# pcb_v3.net
KiCad netlist of a schematic drawn in EAGLE
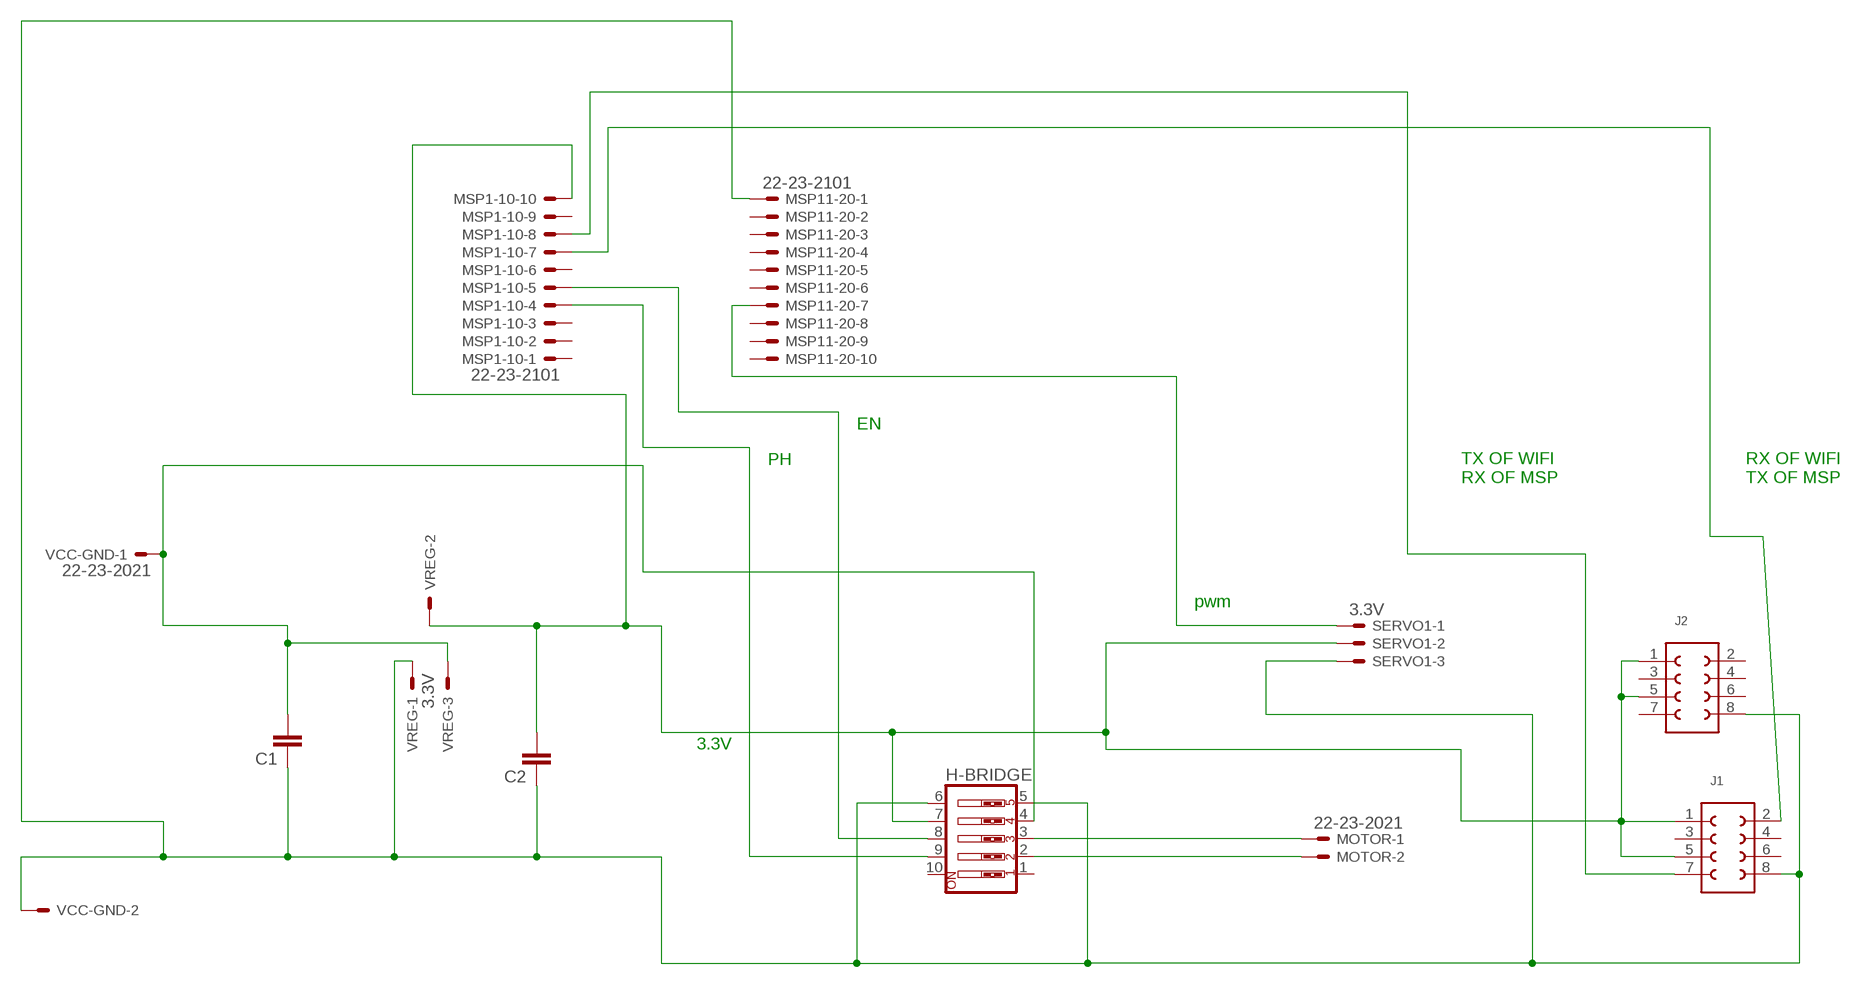
[diagram p0: schematic, sheet 1]

(export (version "E")
  (design (tool "Eeschema 10.0.6"))
  (components
    (comp (ref "C1")
      (value "C2,5-3")
      (footprint "eagle-import:C2.5-3")
      (libsource (lib "eagle-import") (part "C2,5-3"))
    )
    (comp (ref "C2")
      (value "C2,5-3")
      (footprint "eagle-import:C2.5-3")
      (libsource (lib "eagle-import") (part "C2,5-3"))
    )
    (comp (ref "H-BRIDGE")
      (value "SW_DIP-5")
      (footprint "eagle-import:EDG-05")
      (libsource (lib "eagle-import") (part "SW_DIP-5"))
    )
    (comp (ref "J1")
      (value "61300821121")
      (footprint "eagle-import:61300821121")
      (libsource (lib "eagle-import") (part "61300821121"))
    )
    (comp (ref "J2")
      (value "61300821121")
      (footprint "eagle-import:61300821121")
      (libsource (lib "eagle-import") (part "61300821121"))
    )
    (comp (ref "MOTOR")
      (value "22-23-2021")
      (footprint "eagle-import:22-23-2021")
      (fields (field (name "MF") "MOLEX"))
      (libsource (lib "eagle-import") (part "22-23-2021"))
    )
    (comp (ref "MSP1-10")
      (value "22-23-2101")
      (footprint "eagle-import:22-23-2101")
      (fields (field (name "MF") "MOLEX"))
      (libsource (lib "eagle-import") (part "22-23-2101"))
    )
    (comp (ref "MSP11-20")
      (value "22-23-2101")
      (footprint "eagle-import:22-23-2101")
      (fields (field (name "MF") "MOLEX"))
      (libsource (lib "eagle-import") (part "22-23-2101"))
    )
    (comp (ref "SERVO1")
      (value "3.3V")
      (footprint "eagle-import:22-23-2031")
      (fields (field (name "MF") "MOLEX") (field (name "MPN") "22-23-2031"))
      (libsource (lib "eagle-import") (part "22-23-2031"))
    )
    (comp (ref "VCC-GND")
      (value "22-23-2021")
      (footprint "eagle-import:22-23-2021")
      (fields (field (name "MF") "MOLEX"))
      (libsource (lib "eagle-import") (part "22-23-2021"))
    )
    (comp (ref "VREG")
      (value "3.3V")
      (footprint "eagle-import:22-23-2031")
      (fields (field (name "MF") "MOLEX") (field (name "MPN") "22-23-2031"))
      (libsource (lib "eagle-import") (part "22-23-2031"))
    )
  )
  (nets
    (net (code "1") (name "Net-(J1-3)") (class "Default")
      (node (ref "C2") (pin "2") (pinfunction "2_2") (pintype "passive"))
      (node (ref "H-BRIDGE") (pin "7") (pinfunction "7_7") (pintype "passive"))
      (node (ref "J1") (pin "1") (pinfunction "1_1") (pintype "passive"))
      (node (ref "J1") (pin "5") (pinfunction "3_5") (pintype "passive"))
      (node (ref "J2") (pin "1") (pinfunction "1_1") (pintype "passive"))
      (node (ref "J2") (pin "5") (pinfunction "3_5") (pintype "passive"))
      (node (ref "MSP1-10") (pin "10") (pinfunction "S_10") (pintype "passive"))
      (node (ref "SERVO1") (pin "2") (pinfunction "S_2") (pintype "passive"))
      (node (ref "VREG") (pin "2") (pinfunction "S_2") (pintype "passive"))
    )
    (net (code "2") (name "Net-(J1-4)") (class "Default")
      (node (ref "J1") (pin "7") (pinfunction "4_7") (pintype "passive"))
      (node (ref "MSP1-10") (pin "8") (pinfunction "S_8") (pintype "passive"))
    )
    (net (code "3") (name "Net-(J1-5)") (class "Default")
      (node (ref "C1") (pin "1") (pinfunction "1_1") (pintype "passive"))
      (node (ref "C2") (pin "1") (pinfunction "1_1") (pintype "passive"))
      (node (ref "H-BRIDGE") (pin "5") (pinfunction "5_5") (pintype "passive"))
      (node (ref "H-BRIDGE") (pin "6") (pinfunction "6_6") (pintype "passive"))
      (node (ref "J1") (pin "8") (pinfunction "5_8") (pintype "passive"))
      (node (ref "J2") (pin "8") (pinfunction "5_8") (pintype "passive"))
      (node (ref "MSP11-20") (pin "1") (pinfunction "S_1") (pintype "passive"))
      (node (ref "SERVO1") (pin "3") (pinfunction "S_3") (pintype "passive"))
      (node (ref "VCC-GND") (pin "2") (pinfunction "S_2") (pintype "passive"))
      (node (ref "VREG") (pin "1") (pinfunction "S_1") (pintype "passive"))
    )
    (net (code "4") (name "Net-(J1-8)") (class "Default")
      (node (ref "J1") (pin "2") (pinfunction "8_2") (pintype "passive"))
      (node (ref "MSP1-10") (pin "7") (pinfunction "S_7") (pintype "passive"))
    )
    (net (code "5") (name "Net-(MOTORA-S)") (class "Default")
      (node (ref "H-BRIDGE") (pin "3") (pinfunction "3_3") (pintype "passive"))
      (node (ref "MOTOR") (pin "1") (pinfunction "S_1") (pintype "passive"))
    )
    (net (code "6") (name "Net-(MOTORB-S)") (class "Default")
      (node (ref "H-BRIDGE") (pin "2") (pinfunction "2_2") (pintype "passive"))
      (node (ref "MOTOR") (pin "2") (pinfunction "S_2") (pintype "passive"))
    )
    (net (code "7") (name "Net-(MSP1-10E-S)") (class "Default")
      (node (ref "H-BRIDGE") (pin "9") (pinfunction "9_9") (pintype "passive"))
      (node (ref "MSP1-10") (pin "4") (pinfunction "S_4") (pintype "passive"))
    )
    (net (code "8") (name "Net-(MSP1-10F-S)") (class "Default")
      (node (ref "H-BRIDGE") (pin "8") (pinfunction "8_8") (pintype "passive"))
      (node (ref "MSP1-10") (pin "5") (pinfunction "S_5") (pintype "passive"))
    )
    (net (code "9") (name "Net-(MSP11-20H-S)") (class "Default")
      (node (ref "MSP11-20") (pin "7") (pinfunction "S_7") (pintype "passive"))
      (node (ref "SERVO1") (pin "1") (pinfunction "S_1") (pintype "passive"))
    )
    (net (code "10") (name "Net-(VCC-GNDA-S)") (class "Default")
      (node (ref "C1") (pin "2") (pinfunction "2_2") (pintype "passive"))
      (node (ref "H-BRIDGE") (pin "4") (pinfunction "4_4") (pintype "passive"))
      (node (ref "VCC-GND") (pin "1") (pinfunction "S_1") (pintype "passive"))
      (node (ref "VREG") (pin "3") (pinfunction "S_3") (pintype "passive"))
    )
    (net (code "11") (name "unconnected-(H-BRIDGE-Pad1)") (class "Default")
      (node (ref "H-BRIDGE") (pin "1") (pinfunction "1_1") (pintype "passive"))
    )
    (net (code "12") (name "unconnected-(H-BRIDGE-Pad10)") (class "Default")
      (node (ref "H-BRIDGE") (pin "10") (pinfunction "10_10") (pintype "passive"))
    )
    (net (code "13") (name "unconnected-(J1-2-Pad3)") (class "Default")
      (node (ref "J1") (pin "3") (pinfunction "2_3") (pintype "passive"))
    )
    (net (code "14") (name "unconnected-(J1-7-Pad4)") (class "Default")
      (node (ref "J1") (pin "4") (pinfunction "7_4") (pintype "passive"))
    )
    (net (code "15") (name "unconnected-(J1-Pad6)") (class "Default")
      (node (ref "J1") (pin "6") (pinfunction "6_6") (pintype "passive"))
    )
    (net (code "16") (name "unconnected-(J2-2-Pad3)") (class "Default")
      (node (ref "J2") (pin "3") (pinfunction "2_3") (pintype "passive"))
    )
    (net (code "17") (name "unconnected-(J2-4-Pad7)") (class "Default")
      (node (ref "J2") (pin "7") (pinfunction "4_7") (pintype "passive"))
    )
    (net (code "18") (name "unconnected-(J2-7-Pad4)") (class "Default")
      (node (ref "J2") (pin "4") (pinfunction "7_4") (pintype "passive"))
    )
    (net (code "19") (name "unconnected-(J2-8-Pad2)") (class "Default")
      (node (ref "J2") (pin "2") (pinfunction "8_2") (pintype "passive"))
    )
    (net (code "20") (name "unconnected-(J2-Pad6)") (class "Default")
      (node (ref "J2") (pin "6") (pinfunction "6_6") (pintype "passive"))
    )
    (net (code "21") (name "unconnected-(MSP1-10A-S-Pad1)") (class "Default")
      (node (ref "MSP1-10") (pin "1") (pinfunction "S_1") (pintype "passive"))
    )
    (net (code "22") (name "unconnected-(MSP1-10C-S-Pad2)") (class "Default")
      (node (ref "MSP1-10") (pin "2") (pinfunction "S_2") (pintype "passive"))
    )
    (net (code "23") (name "unconnected-(MSP1-10D-S-Pad3)") (class "Default")
      (node (ref "MSP1-10") (pin "3") (pinfunction "S_3") (pintype "passive"))
    )
    (net (code "24") (name "unconnected-(MSP1-10G-S-Pad6)") (class "Default")
      (node (ref "MSP1-10") (pin "6") (pinfunction "S_6") (pintype "passive"))
    )
    (net (code "25") (name "unconnected-(MSP1-10J-S-Pad9)") (class "Default")
      (node (ref "MSP1-10") (pin "9") (pinfunction "S_9") (pintype "passive"))
    )
    (net (code "26") (name "unconnected-(MSP11-20B-S-Pad10)") (class "Default")
      (node (ref "MSP11-20") (pin "10") (pinfunction "S_10") (pintype "passive"))
    )
    (net (code "27") (name "unconnected-(MSP11-20C-S-Pad2)") (class "Default")
      (node (ref "MSP11-20") (pin "2") (pinfunction "S_2") (pintype "passive"))
    )
    (net (code "28") (name "unconnected-(MSP11-20D-S-Pad3)") (class "Default")
      (node (ref "MSP11-20") (pin "3") (pinfunction "S_3") (pintype "passive"))
    )
    (net (code "29") (name "unconnected-(MSP11-20E-S-Pad4)") (class "Default")
      (node (ref "MSP11-20") (pin "4") (pinfunction "S_4") (pintype "passive"))
    )
    (net (code "30") (name "unconnected-(MSP11-20F-S-Pad5)") (class "Default")
      (node (ref "MSP11-20") (pin "5") (pinfunction "S_5") (pintype "passive"))
    )
    (net (code "31") (name "unconnected-(MSP11-20G-S-Pad6)") (class "Default")
      (node (ref "MSP11-20") (pin "6") (pinfunction "S_6") (pintype "passive"))
    )
    (net (code "32") (name "unconnected-(MSP11-20I-S-Pad8)") (class "Default")
      (node (ref "MSP11-20") (pin "8") (pinfunction "S_8") (pintype "passive"))
    )
    (net (code "33") (name "unconnected-(MSP11-20J-S-Pad9)") (class "Default")
      (node (ref "MSP11-20") (pin "9") (pinfunction "S_9") (pintype "passive"))
    )
  )
)
